# SM2200.net
KiCad netlist of a schematic drawn in Altium Designer
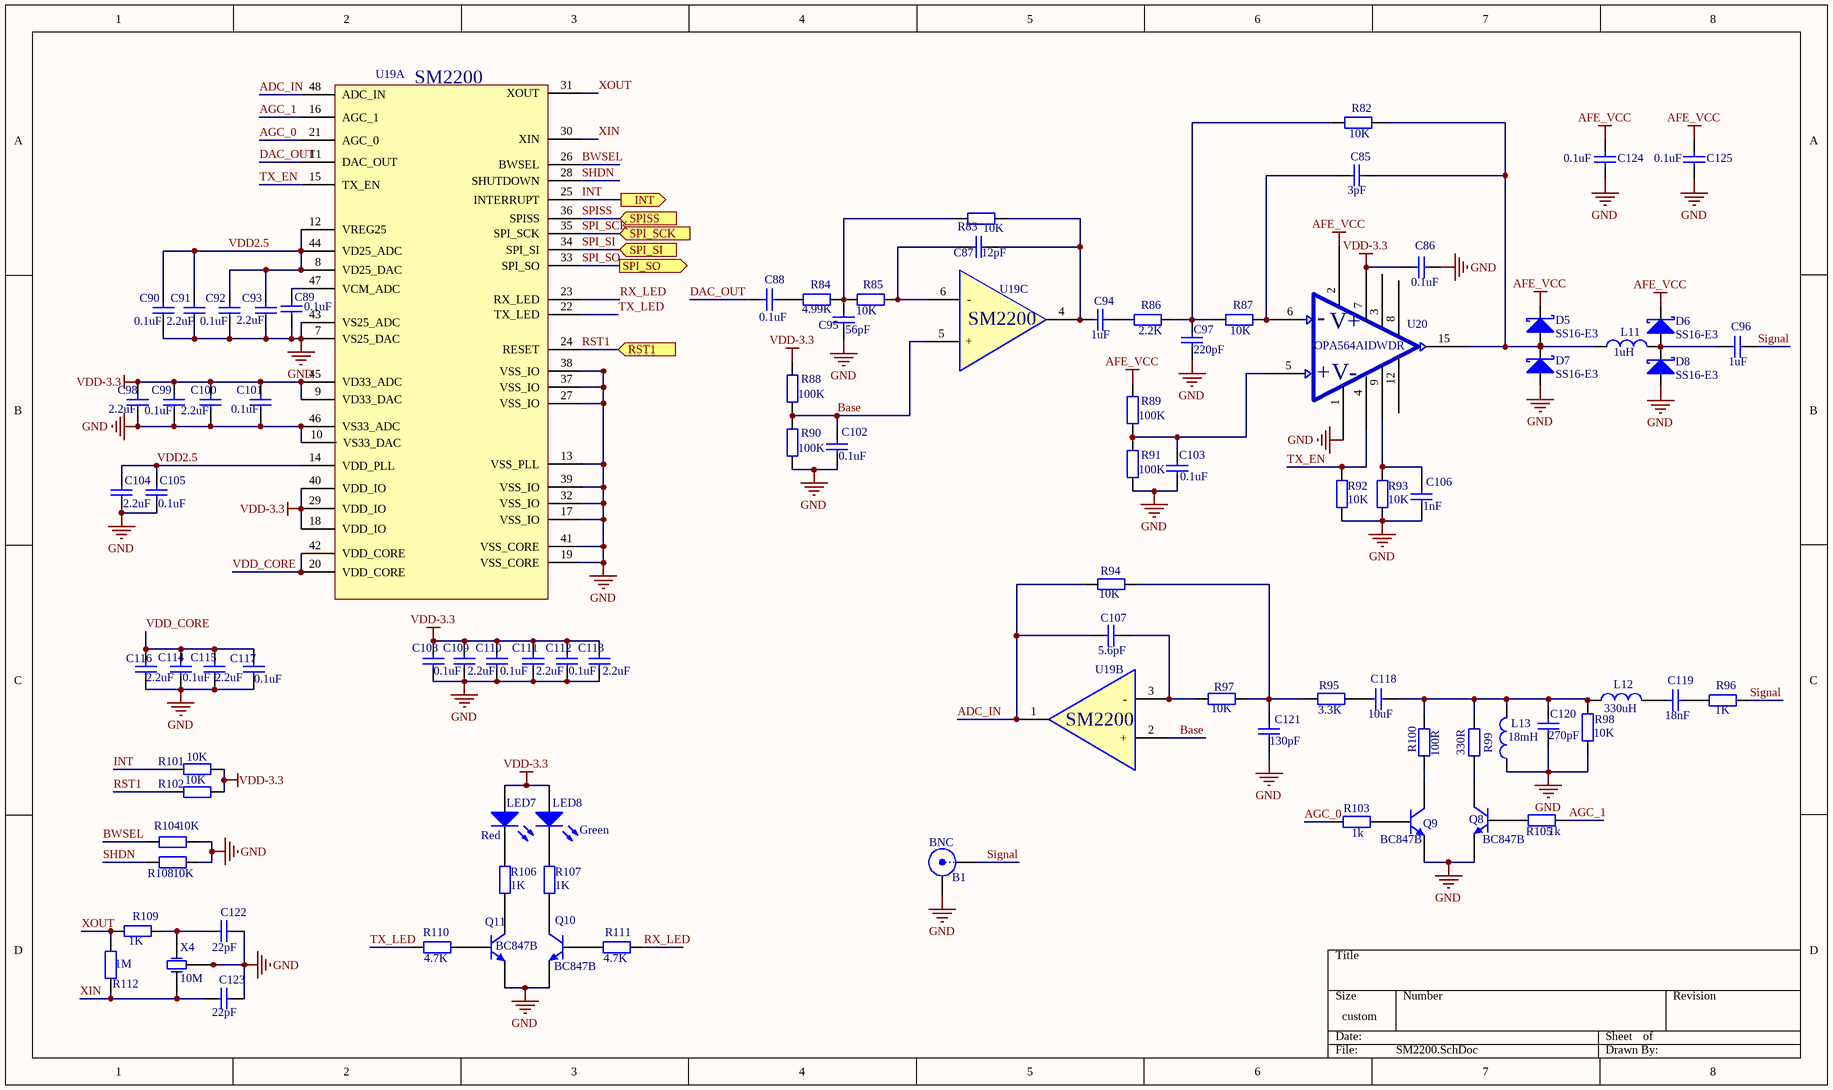
[diagram p0: SM2200.SchDoc]

(export (version "E")
  (design (tool "Eeschema 10.0.6"))
  (components
    (comp (ref "B1")
      (value "BNC")
      (footprint "BNC")
      (fields (field (name "NAME") "BNC"))
      (libsource (lib "原理图库") (part "BNC"))
    )
    (comp (ref "C85")
      (value "3pF")
      (footprint "0603")
      (fields (field (name "Comment") "Capacitor-0603"))
      (libsource (lib "原理图库") (part "Capacitor-0603"))
    )
    (comp (ref "C86")
      (value "0.1uF")
      (footprint "0603")
      (fields (field (name "Comment") "Capacitor-0603"))
      (libsource (lib "原理图库") (part "Capacitor-0603"))
    )
    (comp (ref "C87")
      (value "12pF")
      (footprint "0603")
      (fields (field (name "Comment") "Capacitor-0603"))
      (libsource (lib "原理图库") (part "Capacitor-0603"))
    )
    (comp (ref "C88")
      (value "0.1uF")
      (footprint "0603")
      (fields (field (name "Comment") "Capacitor-0603"))
      (libsource (lib "原理图库") (part "Capacitor-0603"))
    )
    (comp (ref "C89")
      (value "0.1uF")
      (footprint "0603")
      (fields (field (name "Comment") "Capacitor-0805"))
      (libsource (lib "原理图库") (part "Capacitor-0805"))
    )
    (comp (ref "C90")
      (value "0.1uF")
      (footprint "0603")
      (fields (field (name "Comment") "Capacitor-0805"))
      (libsource (lib "原理图库") (part "Capacitor-0805"))
    )
    (comp (ref "C91")
      (value "2.2uF")
      (footprint "0603")
      (fields (field (name "Comment") "Capacitor-0805"))
      (libsource (lib "原理图库") (part "Capacitor-0805"))
    )
    (comp (ref "C92")
      (value "0.1uF")
      (footprint "0603")
      (fields (field (name "Comment") "Capacitor-0805"))
      (libsource (lib "原理图库") (part "Capacitor-0805"))
    )
    (comp (ref "C93")
      (value "2.2uF")
      (footprint "0603")
      (fields (field (name "Comment") "Capacitor-0805"))
      (libsource (lib "原理图库") (part "Capacitor-0805"))
    )
    (comp (ref "C94")
      (value "1uF")
      (footprint "0603")
      (fields (field (name "Comment") "Capacitor-0603"))
      (libsource (lib "原理图库") (part "Capacitor-0603"))
    )
    (comp (ref "C95")
      (value "56pF")
      (footprint "0603")
      (fields (field (name "Comment") "Capacitor-0603"))
      (libsource (lib "原理图库") (part "Capacitor-0603"))
    )
    (comp (ref "C96")
      (value "1uF")
      (footprint "0603")
      (fields (field (name "Comment") "Capacitor-0603"))
      (libsource (lib "原理图库") (part "Capacitor-0603"))
    )
    (comp (ref "C97")
      (value "220pF")
      (footprint "0603")
      (fields (field (name "Comment") "Capacitor-0603"))
      (libsource (lib "原理图库") (part "Capacitor-0603"))
    )
    (comp (ref "C98")
      (value "2.2uF")
      (footprint "0603")
      (fields (field (name "Comment") "Capacitor-0805"))
      (libsource (lib "原理图库") (part "Capacitor-0805"))
    )
    (comp (ref "C99")
      (value "0.1uF")
      (footprint "0603")
      (fields (field (name "Comment") "Capacitor-0805"))
      (libsource (lib "原理图库") (part "Capacitor-0805"))
    )
    (comp (ref "C100")
      (value "2.2uF")
      (footprint "0603")
      (fields (field (name "Comment") "Capacitor-0805"))
      (libsource (lib "原理图库") (part "Capacitor-0805"))
    )
    (comp (ref "C101")
      (value "0.1uF")
      (footprint "0603")
      (fields (field (name "Comment") "Capacitor-0805"))
      (libsource (lib "原理图库") (part "Capacitor-0805"))
    )
    (comp (ref "C102")
      (value "0.1uF")
      (footprint "0603")
      (fields (field (name "Comment") "Capacitor-0603"))
      (libsource (lib "原理图库") (part "Capacitor-0603"))
    )
    (comp (ref "C103")
      (value "0.1uF")
      (footprint "0603")
      (fields (field (name "Comment") "Capacitor-0603"))
      (libsource (lib "原理图库") (part "Capacitor-0603"))
    )
    (comp (ref "C104")
      (value "2.2uF")
      (footprint "0603")
      (fields (field (name "Comment") "Capacitor-0805"))
      (libsource (lib "原理图库") (part "Capacitor-0805"))
    )
    (comp (ref "C105")
      (value "0.1uF")
      (footprint "0603")
      (fields (field (name "Comment") "Capacitor-0805"))
      (libsource (lib "原理图库") (part "Capacitor-0805"))
    )
    (comp (ref "C106")
      (value "1nF")
      (footprint "0603")
      (fields (field (name "Comment") "Capacitor-0603"))
      (libsource (lib "原理图库") (part "Capacitor-0603"))
    )
    (comp (ref "C107")
      (value "5.6pF")
      (footprint "0603")
      (fields (field (name "Comment") "Capacitor-0603"))
      (libsource (lib "原理图库") (part "Capacitor-0603"))
    )
    (comp (ref "C108")
      (value "0.1uF")
      (footprint "0603")
      (fields (field (name "Comment") "Capacitor-0805"))
      (libsource (lib "原理图库") (part "Capacitor-0805"))
    )
    (comp (ref "C109")
      (value "2.2uF")
      (footprint "0603")
      (fields (field (name "Comment") "Capacitor-0805"))
      (libsource (lib "原理图库") (part "Capacitor-0805"))
    )
    (comp (ref "C110")
      (value "0.1uF")
      (footprint "0603")
      (fields (field (name "Comment") "Capacitor-0805"))
      (libsource (lib "原理图库") (part "Capacitor-0805"))
    )
    (comp (ref "C111")
      (value "2.2uF")
      (footprint "0603")
      (fields (field (name "Comment") "Capacitor-0805"))
      (libsource (lib "原理图库") (part "Capacitor-0805"))
    )
    (comp (ref "C112")
      (value "0.1uF")
      (footprint "0603")
      (fields (field (name "Comment") "Capacitor-0805"))
      (libsource (lib "原理图库") (part "Capacitor-0805"))
    )
    (comp (ref "C113")
      (value "2.2uF")
      (footprint "0603")
      (fields (field (name "Comment") "Capacitor-0805"))
      (libsource (lib "原理图库") (part "Capacitor-0805"))
    )
    (comp (ref "C114")
      (value "0.1uF")
      (footprint "0603")
      (fields (field (name "Comment") "Capacitor-0805"))
      (libsource (lib "原理图库") (part "Capacitor-0805"))
    )
    (comp (ref "C115")
      (value "2.2uF")
      (footprint "0603")
      (fields (field (name "Comment") "Capacitor-0805"))
      (libsource (lib "原理图库") (part "Capacitor-0805"))
    )
    (comp (ref "C116")
      (value "2.2uF")
      (footprint "0603")
      (fields (field (name "Comment") "Capacitor-0805"))
      (libsource (lib "原理图库") (part "Capacitor-0805"))
    )
    (comp (ref "C117")
      (value "0.1uF")
      (footprint "0603")
      (fields (field (name "Comment") "Capacitor-0805"))
      (libsource (lib "原理图库") (part "Capacitor-0805"))
    )
    (comp (ref "C118")
      (value "10uF")
      (footprint "0805")
      (fields (field (name "Comment") "Capacitor-0603"))
      (libsource (lib "原理图库") (part "Capacitor-0603"))
    )
    (comp (ref "C119")
      (value "18nF")
      (footprint "0603")
      (fields (field (name "Comment") "Capacitor-0603"))
      (libsource (lib "原理图库") (part "Capacitor-0603"))
    )
    (comp (ref "C120")
      (value "270pF")
      (footprint "0603")
      (fields (field (name "Comment") "Capacitor-0603"))
      (libsource (lib "原理图库") (part "Capacitor-0603"))
    )
    (comp (ref "C121")
      (value "130pF")
      (footprint "0603")
      (fields (field (name "Comment") "Capacitor-0603"))
      (libsource (lib "原理图库") (part "Capacitor-0603"))
    )
    (comp (ref "C122")
      (value "22pF")
      (footprint "0603")
      (fields (field (name "Comment") "Capacitor-0805"))
      (libsource (lib "原理图库") (part "Capacitor-0805"))
    )
    (comp (ref "C123")
      (value "22pF")
      (footprint "0603")
      (fields (field (name "Comment") "Capacitor-0805"))
      (libsource (lib "原理图库") (part "Capacitor-0805"))
    )
    (comp (ref "C124")
      (value "0.1uF")
      (footprint "0603")
      (fields (field (name "Comment") "Capacitor-0603"))
      (libsource (lib "原理图库") (part "Capacitor-0603"))
    )
    (comp (ref "C125")
      (value "0.1uF")
      (footprint "0603")
      (fields (field (name "Comment") "Capacitor-0603"))
      (libsource (lib "原理图库") (part "Capacitor-0603"))
    )
    (comp (ref "D5")
      (value "SSA34")
      (footprint "IN5824")
      (fields (field (name "NAME") "SS16-E3"))
      (libsource (lib "原理图库") (part "SSA34"))
    )
    (comp (ref "D6")
      (value "SSA34")
      (footprint "IN5824")
      (fields (field (name "NAME") "SS16-E3"))
      (libsource (lib "原理图库") (part "SSA34"))
    )
    (comp (ref "D7")
      (value "SSA34")
      (footprint "IN5824")
      (fields (field (name "NAME") "SS16-E3"))
      (libsource (lib "原理图库") (part "SSA34"))
    )
    (comp (ref "D8")
      (value "SSA34")
      (footprint "IN5824")
      (fields (field (name "NAME") "SS16-E3"))
      (libsource (lib "原理图库") (part "SSA34"))
    )
    (comp (ref "L11")
      (value "1uH")
      (footprint "1206")
      (fields (field (name "Comment") "Inductor"))
      (libsource (lib "原理图库") (part "Inductor"))
    )
    (comp (ref "L12")
      (value "330uH")
      (footprint "Inductor(7.8*7*5)")
      (fields (field (name "Comment") "Inductor"))
      (libsource (lib "原理图库") (part "Inductor"))
    )
    (comp (ref "L13")
      (value "18mH")
      (footprint "工字电感0608")
      (fields (field (name "Comment") "Inductor"))
      (libsource (lib "原理图库") (part "Inductor"))
    )
    (comp (ref "LED7")
      (value "LED")
      (footprint "外插小灯")
      (fields (field (name "COLOR") "Red"))
      (libsource (lib "原理图库") (part "LED"))
    )
    (comp (ref "LED8")
      (value "LED")
      (footprint "外插小灯")
      (fields (field (name "COLOR") "Green"))
      (libsource (lib "原理图库") (part "LED"))
    )
    (comp (ref "Q8")
      (value "BC847")
      (footprint "BC847B")
      (fields (field (name "NAME") "BC847B"))
      (libsource (lib "原理图库") (part "BC847"))
    )
    (comp (ref "Q9")
      (value "BC847")
      (footprint "BC847B")
      (fields (field (name "NAME") "BC847B"))
      (libsource (lib "原理图库") (part "BC847"))
    )
    (comp (ref "Q10")
      (value "BC847")
      (footprint "BC847B")
      (fields (field (name "NAME") "BC847B"))
      (libsource (lib "原理图库") (part "BC847"))
    )
    (comp (ref "Q11")
      (value "BC847")
      (footprint "BC847B")
      (fields (field (name "NAME") "BC847B"))
      (libsource (lib "原理图库") (part "BC847"))
    )
    (comp (ref "R82")
      (value "10K")
      (footprint "0603")
      (fields (field (name "Comment") "Resistor-0603"))
      (libsource (lib "原理图库") (part "Resistor-0603"))
    )
    (comp (ref "R83")
      (value "10K")
      (footprint "0603")
      (fields (field (name "Comment") "Resistor-0603"))
      (libsource (lib "原理图库") (part "Resistor-0603"))
    )
    (comp (ref "R84")
      (value "4.99K")
      (footprint "0603")
      (fields (field (name "Comment") "Resistor-0603"))
      (libsource (lib "原理图库") (part "Resistor-0603"))
    )
    (comp (ref "R85")
      (value "10K")
      (footprint "0603")
      (fields (field (name "Comment") "Resistor-0603"))
      (libsource (lib "原理图库") (part "Resistor-0603"))
    )
    (comp (ref "R86")
      (value "2.2K")
      (footprint "0603")
      (fields (field (name "Comment") "Resistor-0603"))
      (libsource (lib "原理图库") (part "Resistor-0603"))
    )
    (comp (ref "R87")
      (value "10K")
      (footprint "0603")
      (fields (field (name "Comment") "Resistor-0603"))
      (libsource (lib "原理图库") (part "Resistor-0603"))
    )
    (comp (ref "R88")
      (value "100K")
      (footprint "0603")
      (fields (field (name "Comment") "Resistor-0603"))
      (libsource (lib "") (part "Resistor-0603_2"))
    )
    (comp (ref "R89")
      (value "100K")
      (footprint "0603")
      (fields (field (name "Comment") "Resistor-0603"))
      (libsource (lib "") (part "Resistor-0603_2"))
    )
    (comp (ref "R90")
      (value "100K")
      (footprint "0603")
      (fields (field (name "Comment") "Resistor-0603"))
      (libsource (lib "") (part "Resistor-0603_2"))
    )
    (comp (ref "R91")
      (value "100K")
      (footprint "0603")
      (fields (field (name "Comment") "Resistor-0603"))
      (libsource (lib "") (part "Resistor-0603_2"))
    )
    (comp (ref "R92")
      (value "10K")
      (footprint "0603")
      (fields (field (name "Comment") "Resistor-0603"))
      (libsource (lib "") (part "Resistor-0603_2"))
    )
    (comp (ref "R93")
      (value "10K")
      (footprint "0603")
      (fields (field (name "Comment") "Resistor-0603"))
      (libsource (lib "") (part "Resistor-0603_2"))
    )
    (comp (ref "R94")
      (value "10K")
      (footprint "0603")
      (fields (field (name "Comment") "Resistor-0603"))
      (libsource (lib "") (part "Resistor-0603_1"))
    )
    (comp (ref "R95")
      (value "3.3K")
      (footprint "0603")
      (fields (field (name "Comment") "Resistor-0603"))
      (libsource (lib "") (part "Resistor-0603_1"))
    )
    (comp (ref "R96")
      (value "1K")
      (footprint "0603")
      (fields (field (name "Comment") "Resistor-0603"))
      (libsource (lib "原理图库") (part "Resistor-0603"))
    )
    (comp (ref "R97")
      (value "10K")
      (footprint "0603")
      (fields (field (name "Comment") "Resistor-0603"))
      (libsource (lib "") (part "Resistor-0603_1"))
    )
    (comp (ref "R98")
      (value "10K")
      (footprint "0603")
      (fields (field (name "Comment") "Resistor-0603"))
      (libsource (lib "") (part "Resistor-0603_2"))
    )
    (comp (ref "R99")
      (value "330R")
      (footprint "0603")
      (fields (field (name "Comment") "Resistor-0603"))
      (libsource (lib "") (part "Resistor-0603_2"))
    )
    (comp (ref "R100")
      (value "100R")
      (footprint "0603")
      (fields (field (name "Comment") "Resistor-0603"))
      (libsource (lib "") (part "Resistor-0603_2"))
    )
    (comp (ref "R101")
      (value "10K")
      (footprint "0603")
      (fields (field (name "Comment") "Resistor-0805"))
      (libsource (lib "") (part "Resistor-0805_1"))
    )
    (comp (ref "R102")
      (value "10K")
      (footprint "0603")
      (fields (field (name "Comment") "Resistor-0805"))
      (libsource (lib "") (part "Resistor-0805_1"))
    )
    (comp (ref "R103")
      (value "1k")
      (footprint "0603")
      (fields (field (name "Comment") "Resistor-0603"))
      (libsource (lib "") (part "Resistor-0603_1"))
    )
    (comp (ref "R104")
      (value "10K")
      (footprint "0603")
      (fields (field (name "Comment") "Resistor-0805"))
      (libsource (lib "") (part "Resistor-0805_1"))
    )
    (comp (ref "R105")
      (value "1k")
      (footprint "0603")
      (fields (field (name "Comment") "Resistor-0603"))
      (libsource (lib "原理图库") (part "Resistor-0603"))
    )
    (comp (ref "R106")
      (value "1K")
      (footprint "0603")
      (fields (field (name "Comment") "Resistor-0805"))
      (libsource (lib "原理图库") (part "Resistor-0805"))
    )
    (comp (ref "R107")
      (value "1K")
      (footprint "0603")
      (fields (field (name "Comment") "Resistor-0805"))
      (libsource (lib "原理图库") (part "Resistor-0805"))
    )
    (comp (ref "R108")
      (value "10K")
      (footprint "0603")
      (fields (field (name "Comment") "Resistor-0805"))
      (libsource (lib "") (part "Resistor-0805_1"))
    )
    (comp (ref "R109")
      (value "1K")
      (footprint "0603")
      (fields (field (name "Comment") "Resistor-0805"))
      (libsource (lib "") (part "Resistor-0805_1"))
    )
    (comp (ref "R110")
      (value "4.7K")
      (footprint "0603")
      (fields (field (name "Comment") "Resistor-0805"))
      (libsource (lib "") (part "Resistor-0805_2"))
    )
    (comp (ref "R111")
      (value "4.7K")
      (footprint "0603")
      (fields (field (name "Comment") "Resistor-0805"))
      (libsource (lib "") (part "Resistor-0805_2"))
    )
    (comp (ref "R112")
      (value "1M")
      (footprint "0603")
      (fields (field (name "Comment") "Resistor-0805"))
      (libsource (lib "原理图库") (part "Resistor-0805"))
    )
    (comp (ref "U19")
      (value "SM2200")
      (footprint "SM2200")
      (fields (field (name "ALTIUM_UNNAMED_1") "SM2200"))
      (libsource (lib "") (part "SM2200_1"))
    )
    (comp (ref "U20")
      (value "OPA564AIDWDR")
      (footprint "OPA564AIDWDR")
      (fields (field (name "NAME") "OPA564AIDWDR"))
      (libsource (lib "原理图库") (part "OPA564AIDWDR"))
    )
    (comp (ref "X4")
      (value "10M")
      (footprint "3225无源晶振")
      (fields (field (name "Comment") "3225无源晶振"))
      (libsource (lib "原理图库") (part "3225无源晶振"))
    )
  )
  (nets
    (net (code "1") (name "/ADC_IN") (class "Default")
      (node (ref "C107") (pin "1") (pinfunction "1_1") (pintype "passive"))
      (node (ref "R94") (pin "2") (pinfunction "2_2") (pintype "passive"))
      (node (ref "U19") (pin "1") (pintype "passive"))
      (node (ref "U19") (pin "48") (pinfunction "ADC_IN_48") (pintype "passive"))
    )
    (net (code "2") (name "/AGC_0") (class "Default")
      (node (ref "R103") (pin "2") (pinfunction "2_2") (pintype "passive"))
      (node (ref "U19") (pin "21") (pinfunction "AGC_0_21") (pintype "passive"))
    )
    (net (code "3") (name "/AGC_1") (class "Default")
      (node (ref "R105") (pin "2") (pinfunction "2_2") (pintype "passive"))
      (node (ref "U19") (pin "16") (pinfunction "AGC_1_16") (pintype "passive"))
    )
    (net (code "4") (name "/BWSEL") (class "Default")
      (node (ref "R104") (pin "1") (pinfunction "1_1") (pintype "passive"))
      (node (ref "U19") (pin "26") (pinfunction "BWSEL_26") (pintype "passive"))
    )
    (net (code "5") (name "/Base") (class "Default")
      (node (ref "C102") (pin "2") (pinfunction "2_2") (pintype "passive"))
      (node (ref "R88") (pin "1") (pinfunction "1_1") (pintype "passive"))
      (node (ref "R90") (pin "2") (pinfunction "2_2") (pintype "passive"))
      (node (ref "U19") (pin "2") (pinfunction "+_2") (pintype "passive"))
      (node (ref "U19") (pin "5") (pinfunction "+_5") (pintype "passive"))
    )
    (net (code "6") (name "/DAC_OUT") (class "Default")
      (node (ref "C88") (pin "2") (pinfunction "2_2") (pintype "passive"))
      (node (ref "U19") (pin "11") (pinfunction "DAC_OUT_11") (pintype "passive"))
    )
    (net (code "7") (name "/INT") (class "Default")
      (node (ref "R101") (pin "1") (pinfunction "1_1") (pintype "passive"))
      (node (ref "U19") (pin "25") (pinfunction "INTERRUPT_25") (pintype "passive"))
    )
    (net (code "8") (name "/RST1") (class "Default")
      (node (ref "R102") (pin "1") (pinfunction "1_1") (pintype "passive"))
      (node (ref "U19") (pin "24") (pinfunction "RESET_24") (pintype "passive"))
    )
    (net (code "9") (name "/RX_LED") (class "Default")
      (node (ref "R111") (pin "1") (pinfunction "1_1") (pintype "passive"))
      (node (ref "U19") (pin "23") (pinfunction "RX_LED_23") (pintype "passive"))
    )
    (net (code "10") (name "/SHDN") (class "Default")
      (node (ref "R108") (pin "1") (pinfunction "1_1") (pintype "passive"))
      (node (ref "U19") (pin "28") (pinfunction "SHUTDOWN_28") (pintype "passive"))
    )
    (net (code "11") (name "/SPISS") (class "Default")
      (node (ref "U19") (pin "36") (pinfunction "SPISS_36") (pintype "passive"))
    )
    (net (code "12") (name "/SPI_SCK") (class "Default")
      (node (ref "U19") (pin "35") (pinfunction "SPI_SCK_35") (pintype "passive"))
    )
    (net (code "13") (name "/SPI_SI") (class "Default")
      (node (ref "U19") (pin "34") (pinfunction "SPI_SI_34") (pintype "passive"))
    )
    (net (code "14") (name "/SPI_SO") (class "Default")
      (node (ref "U19") (pin "33") (pinfunction "SPI_SO_33") (pintype "passive"))
    )
    (net (code "15") (name "/Signal") (class "Default")
      (node (ref "B1") (pin "2") (pinfunction "X_2") (pintype "passive"))
      (node (ref "C96") (pin "1") (pinfunction "1_1") (pintype "passive"))
      (node (ref "R96") (pin "2") (pinfunction "2_2") (pintype "passive"))
    )
    (net (code "16") (name "/TX_EN") (class "Default")
      (node (ref "R92") (pin "2") (pinfunction "2_2") (pintype "passive"))
      (node (ref "U19") (pin "15") (pinfunction "TX_EN_15") (pintype "passive"))
      (node (ref "U20") (pin "4") (pintype "passive"))
    )
    (net (code "17") (name "/TX_LED") (class "Default")
      (node (ref "R110") (pin "2") (pinfunction "2_2") (pintype "passive"))
      (node (ref "U19") (pin "22") (pinfunction "TX_LED_22") (pintype "passive"))
    )
    (net (code "18") (name "/VDD2.5") (class "Default")
      (node (ref "C104") (pin "2") (pinfunction "2_2") (pintype "passive"))
      (node (ref "C105") (pin "2") (pinfunction "2_2") (pintype "passive"))
      (node (ref "C90") (pin "2") (pinfunction "2_2") (pintype "passive"))
      (node (ref "C91") (pin "2") (pinfunction "2_2") (pintype "passive"))
      (node (ref "C92") (pin "2") (pinfunction "2_2") (pintype "passive"))
      (node (ref "C93") (pin "2") (pinfunction "2_2") (pintype "passive"))
      (node (ref "U19") (pin "12") (pinfunction "VREG25_12") (pintype "passive"))
      (node (ref "U19") (pin "14") (pinfunction "VDD_PLL_14") (pintype "passive"))
      (node (ref "U19") (pin "44") (pinfunction "VD25_ADC_44") (pintype "passive"))
      (node (ref "U19") (pin "8") (pinfunction "VD25_DAC_8") (pintype "passive"))
    )
    (net (code "19") (name "/VDD_CORE") (class "Default")
      (node (ref "C114") (pin "2") (pinfunction "2_2") (pintype "passive"))
      (node (ref "C115") (pin "2") (pinfunction "2_2") (pintype "passive"))
      (node (ref "C116") (pin "2") (pinfunction "2_2") (pintype "passive"))
      (node (ref "C117") (pin "2") (pinfunction "2_2") (pintype "passive"))
      (node (ref "U19") (pin "20") (pinfunction "VDD_CORE_20") (pintype "passive"))
      (node (ref "U19") (pin "42") (pinfunction "VDD_CORE_42") (pintype "passive"))
    )
    (net (code "20") (name "/XIN") (class "Default")
      (node (ref "C123") (pin "1") (pinfunction "1_1") (pintype "passive"))
      (node (ref "R112") (pin "1") (pinfunction "1_1") (pintype "passive"))
      (node (ref "U19") (pin "30") (pinfunction "XIN_30") (pintype "passive"))
      (node (ref "X4") (pin "1") (pinfunction "OSC1_1") (pintype "passive"))
    )
    (net (code "21") (name "/XOUT") (class "Default")
      (node (ref "R109") (pin "1") (pinfunction "1_1") (pintype "passive"))
      (node (ref "R112") (pin "2") (pinfunction "2_2") (pintype "passive"))
      (node (ref "U19") (pin "31") (pinfunction "XOUT_31") (pintype "passive"))
    )
    (net (code "22") (name "AFE_VCC") (class "Default")
      (node (ref "C124") (pin "2") (pinfunction "2_2") (pintype "passive"))
      (node (ref "C125") (pin "2") (pinfunction "2_2") (pintype "passive"))
      (node (ref "D5") (pin "2") (pinfunction "K_2") (pintype "passive"))
      (node (ref "D6") (pin "2") (pinfunction "K_2") (pintype "passive"))
      (node (ref "R89") (pin "2") (pinfunction "2_2") (pintype "passive"))
      (node (ref "U20") (pin "2") (pintype "passive"))
    )
    (net (code "23") (name "GND") (class "Default")
      (node (ref "B1") (pin "1") (pinfunction "Y_1") (pintype "passive"))
      (node (ref "C100") (pin "1") (pinfunction "1_1") (pintype "passive"))
      (node (ref "C101") (pin "1") (pinfunction "1_1") (pintype "passive"))
      (node (ref "C102") (pin "1") (pinfunction "1_1") (pintype "passive"))
      (node (ref "C103") (pin "2") (pinfunction "2_2") (pintype "passive"))
      (node (ref "C104") (pin "1") (pinfunction "1_1") (pintype "passive"))
      (node (ref "C105") (pin "1") (pinfunction "1_1") (pintype "passive"))
      (node (ref "C106") (pin "1") (pinfunction "1_1") (pintype "passive"))
      (node (ref "C108") (pin "1") (pinfunction "1_1") (pintype "passive"))
      (node (ref "C109") (pin "1") (pinfunction "1_1") (pintype "passive"))
      (node (ref "C110") (pin "1") (pinfunction "1_1") (pintype "passive"))
      (node (ref "C111") (pin "1") (pinfunction "1_1") (pintype "passive"))
      (node (ref "C112") (pin "1") (pinfunction "1_1") (pintype "passive"))
      (node (ref "C113") (pin "1") (pinfunction "1_1") (pintype "passive"))
      (node (ref "C114") (pin "1") (pinfunction "1_1") (pintype "passive"))
      (node (ref "C115") (pin "1") (pinfunction "1_1") (pintype "passive"))
      (node (ref "C116") (pin "1") (pinfunction "1_1") (pintype "passive"))
      (node (ref "C117") (pin "1") (pinfunction "1_1") (pintype "passive"))
      (node (ref "C120") (pin "2") (pinfunction "2_2") (pintype "passive"))
      (node (ref "C121") (pin "2") (pinfunction "2_2") (pintype "passive"))
      (node (ref "C122") (pin "2") (pinfunction "2_2") (pintype "passive"))
      (node (ref "C123") (pin "2") (pinfunction "2_2") (pintype "passive"))
      (node (ref "C124") (pin "1") (pinfunction "1_1") (pintype "passive"))
      (node (ref "C125") (pin "1") (pinfunction "1_1") (pintype "passive"))
      (node (ref "C86") (pin "1") (pinfunction "1_1") (pintype "passive"))
      (node (ref "C89") (pin "1") (pinfunction "1_1") (pintype "passive"))
      (node (ref "C90") (pin "1") (pinfunction "1_1") (pintype "passive"))
      (node (ref "C91") (pin "1") (pinfunction "1_1") (pintype "passive"))
      (node (ref "C92") (pin "1") (pinfunction "1_1") (pintype "passive"))
      (node (ref "C93") (pin "1") (pinfunction "1_1") (pintype "passive"))
      (node (ref "C95") (pin "1") (pinfunction "1_1") (pintype "passive"))
      (node (ref "C97") (pin "2") (pinfunction "2_2") (pintype "passive"))
      (node (ref "C98") (pin "1") (pinfunction "1_1") (pintype "passive"))
      (node (ref "C99") (pin "1") (pinfunction "1_1") (pintype "passive"))
      (node (ref "D7") (pin "1") (pinfunction "A_1") (pintype "passive"))
      (node (ref "D8") (pin "1") (pinfunction "A_1") (pintype "passive"))
      (node (ref "L13") (pin "1") (pinfunction "1_1") (pintype "passive"))
      (node (ref "Q10") (pin "1") (pinfunction "E_1") (pintype "passive"))
      (node (ref "Q11") (pin "1") (pinfunction "E_1") (pintype "passive"))
      (node (ref "Q8") (pin "1") (pinfunction "E_1") (pintype "passive"))
      (node (ref "Q9") (pin "1") (pinfunction "E_1") (pintype "passive"))
      (node (ref "R104") (pin "2") (pinfunction "2_2") (pintype "passive"))
      (node (ref "R108") (pin "2") (pinfunction "2_2") (pintype "passive"))
      (node (ref "R90") (pin "1") (pinfunction "1_1") (pintype "passive"))
      (node (ref "R91") (pin "1") (pinfunction "1_1") (pintype "passive"))
      (node (ref "R92") (pin "1") (pinfunction "1_1") (pintype "passive"))
      (node (ref "R93") (pin "1") (pinfunction "1_1") (pintype "passive"))
      (node (ref "R98") (pin "1") (pinfunction "1_1") (pintype "passive"))
      (node (ref "U19") (pin "10") (pinfunction "VS33_DAC_10") (pintype "passive"))
      (node (ref "U19") (pin "13") (pinfunction "VSS_PLL_13") (pintype "passive"))
      (node (ref "U19") (pin "17") (pinfunction "VSS_IO_17") (pintype "passive"))
      (node (ref "U19") (pin "19") (pinfunction "VSS_CORE_19") (pintype "passive"))
      (node (ref "U19") (pin "27") (pinfunction "VSS_IO_27") (pintype "passive"))
      (node (ref "U19") (pin "32") (pinfunction "VSS_IO_32") (pintype "passive"))
      (node (ref "U19") (pin "37") (pinfunction "VSS_IO_37") (pintype "passive"))
      (node (ref "U19") (pin "38") (pinfunction "VSS_IO_38") (pintype "passive"))
      (node (ref "U19") (pin "39") (pinfunction "VSS_IO_39") (pintype "passive"))
      (node (ref "U19") (pin "41") (pinfunction "VSS_CORE_41") (pintype "passive"))
      (node (ref "U19") (pin "43") (pinfunction "VS25_ADC_43") (pintype "passive"))
      (node (ref "U19") (pin "46") (pinfunction "VS33_ADC_46") (pintype "passive"))
      (node (ref "U19") (pin "7") (pinfunction "VS25_DAC_7") (pintype "passive"))
      (node (ref "U20") (pin "1") (pintype "passive"))
      (node (ref "X4") (pin "2") (pinfunction "GND_2") (pintype "passive"))
      (node (ref "X4") (pin "4") (pinfunction "GND_4") (pintype "passive"))
    )
    (net (code "24") (name "Net-(C87-Pad1)") (class "Default")
      (node (ref "C87") (pin "1") (pinfunction "1_1") (pintype "passive"))
      (node (ref "C94") (pin "2") (pinfunction "2_2") (pintype "passive"))
      (node (ref "R83") (pin "2") (pinfunction "2_2") (pintype "passive"))
      (node (ref "U19") (pin "4") (pintype "passive"))
    )
    (net (code "25") (name "Net-(C88-Pad1)") (class "Default")
      (node (ref "C88") (pin "1") (pinfunction "1_1") (pintype "passive"))
      (node (ref "R84") (pin "1") (pinfunction "1_1") (pintype "passive"))
    )
    (net (code "26") (name "Net-(C94-Pad1)") (class "Default")
      (node (ref "C94") (pin "1") (pinfunction "1_1") (pintype "passive"))
      (node (ref "R86") (pin "1") (pinfunction "1_1") (pintype "passive"))
    )
    (net (code "27") (name "Net-(C95-Pad2)") (class "Default")
      (node (ref "C95") (pin "2") (pinfunction "2_2") (pintype "passive"))
      (node (ref "R83") (pin "1") (pinfunction "1_1") (pintype "passive"))
      (node (ref "R84") (pin "2") (pinfunction "2_2") (pintype "passive"))
      (node (ref "R85") (pin "1") (pinfunction "1_1") (pintype "passive"))
    )
    (net (code "28") (name "Net-(C97-Pad1)") (class "Default")
      (node (ref "C97") (pin "1") (pinfunction "1_1") (pintype "passive"))
      (node (ref "R82") (pin "1") (pinfunction "1_1") (pintype "passive"))
      (node (ref "R86") (pin "2") (pinfunction "2_2") (pintype "passive"))
      (node (ref "R87") (pin "1") (pinfunction "1_1") (pintype "passive"))
    )
    (net (code "29") (name "Net-(C106-Pad2)") (class "Default")
      (node (ref "C106") (pin "2") (pinfunction "2_2") (pintype "passive"))
      (node (ref "R93") (pin "2") (pinfunction "2_2") (pintype "passive"))
      (node (ref "U20") (pin "9") (pintype "passive"))
    )
    (net (code "30") (name "Net-(C118-Pad1)") (class "Default")
      (node (ref "C118") (pin "1") (pinfunction "1_1") (pintype "passive"))
      (node (ref "C120") (pin "1") (pinfunction "1_1") (pintype "passive"))
      (node (ref "L12") (pin "1") (pinfunction "1_1") (pintype "passive"))
      (node (ref "L13") (pin "2") (pinfunction "2_2") (pintype "passive"))
      (node (ref "R100") (pin "2") (pinfunction "2_2") (pintype "passive"))
      (node (ref "R98") (pin "2") (pinfunction "2_2") (pintype "passive"))
      (node (ref "R99") (pin "2") (pinfunction "2_2") (pintype "passive"))
    )
    (net (code "31") (name "Net-(C118-Pad2)") (class "Default")
      (node (ref "C118") (pin "2") (pinfunction "2_2") (pintype "passive"))
      (node (ref "R95") (pin "1") (pinfunction "1_1") (pintype "passive"))
    )
    (net (code "32") (name "Net-(C119-Pad1)") (class "Default")
      (node (ref "C119") (pin "1") (pinfunction "1_1") (pintype "passive"))
      (node (ref "R96") (pin "1") (pinfunction "1_1") (pintype "passive"))
    )
    (net (code "33") (name "Net-(C119-Pad2)") (class "Default")
      (node (ref "C119") (pin "2") (pinfunction "2_2") (pintype "passive"))
      (node (ref "L12") (pin "2") (pinfunction "2_2") (pintype "passive"))
    )
    (net (code "34") (name "Net-(C121-Pad1)") (class "Default")
      (node (ref "C121") (pin "1") (pinfunction "1_1") (pintype "passive"))
      (node (ref "R94") (pin "1") (pinfunction "1_1") (pintype "passive"))
      (node (ref "R95") (pin "2") (pinfunction "2_2") (pintype "passive"))
      (node (ref "R97") (pin "1") (pinfunction "1_1") (pintype "passive"))
    )
    (net (code "35") (name "Net-(D5-A)") (class "Default")
      (node (ref "C85") (pin "1") (pinfunction "1_1") (pintype "passive"))
      (node (ref "D5") (pin "1") (pinfunction "A_1") (pintype "passive"))
      (node (ref "D7") (pin "2") (pinfunction "K_2") (pintype "passive"))
      (node (ref "L11") (pin "1") (pinfunction "1_1") (pintype "passive"))
      (node (ref "R82") (pin "2") (pinfunction "2_2") (pintype "passive"))
      (node (ref "U20") (pin "15") (pintype "passive"))
    )
    (net (code "36") (name "Net-(D6-A)") (class "Default")
      (node (ref "C96") (pin "2") (pinfunction "2_2") (pintype "passive"))
      (node (ref "D6") (pin "1") (pinfunction "A_1") (pintype "passive"))
      (node (ref "D8") (pin "2") (pinfunction "K_2") (pintype "passive"))
      (node (ref "L11") (pin "2") (pinfunction "2_2") (pintype "passive"))
    )
    (net (code "37") (name "Net-(LED7-Pad2)") (class "Default")
      (node (ref "LED7") (pin "2") (pinfunction "2_2") (pintype "passive"))
      (node (ref "R106") (pin "2") (pinfunction "2_2") (pintype "passive"))
    )
    (net (code "38") (name "Net-(LED8-Pad2)") (class "Default")
      (node (ref "LED8") (pin "2") (pinfunction "2_2") (pintype "passive"))
      (node (ref "R107") (pin "2") (pinfunction "2_2") (pintype "passive"))
    )
    (net (code "39") (name "Net-(Q8-B)") (class "Default")
      (node (ref "Q8") (pin "2") (pinfunction "B_2") (pintype "passive"))
      (node (ref "R105") (pin "1") (pinfunction "1_1") (pintype "passive"))
    )
    (net (code "40") (name "Net-(Q8-C)") (class "Default")
      (node (ref "Q8") (pin "3") (pinfunction "C_3") (pintype "passive"))
      (node (ref "R99") (pin "1") (pinfunction "1_1") (pintype "passive"))
    )
    (net (code "41") (name "Net-(Q9-B)") (class "Default")
      (node (ref "Q9") (pin "2") (pinfunction "B_2") (pintype "passive"))
      (node (ref "R103") (pin "1") (pinfunction "1_1") (pintype "passive"))
    )
    (net (code "42") (name "Net-(Q9-C)") (class "Default")
      (node (ref "Q9") (pin "3") (pinfunction "C_3") (pintype "passive"))
      (node (ref "R100") (pin "1") (pinfunction "1_1") (pintype "passive"))
    )
    (net (code "43") (name "Net-(Q10-B)") (class "Default")
      (node (ref "Q10") (pin "2") (pinfunction "B_2") (pintype "passive"))
      (node (ref "R111") (pin "2") (pinfunction "2_2") (pintype "passive"))
    )
    (net (code "44") (name "Net-(Q10-C)") (class "Default")
      (node (ref "Q10") (pin "3") (pinfunction "C_3") (pintype "passive"))
      (node (ref "R107") (pin "1") (pinfunction "1_1") (pintype "passive"))
    )
    (net (code "45") (name "Net-(Q11-B)") (class "Default")
      (node (ref "Q11") (pin "2") (pinfunction "B_2") (pintype "passive"))
      (node (ref "R110") (pin "1") (pinfunction "1_1") (pintype "passive"))
    )
    (net (code "46") (name "Net-(Q11-C)") (class "Default")
      (node (ref "Q11") (pin "3") (pinfunction "C_3") (pintype "passive"))
      (node (ref "R106") (pin "1") (pinfunction "1_1") (pintype "passive"))
    )
    (net (code "47") (name "Net-(U19A-VCM_ADC)") (class "Default")
      (node (ref "C89") (pin "2") (pinfunction "2_2") (pintype "passive"))
      (node (ref "U19") (pin "47") (pinfunction "VCM_ADC_47") (pintype "passive"))
    )
    (net (code "48") (name "Net-(U19B--)") (class "Default")
      (node (ref "C107") (pin "2") (pinfunction "2_2") (pintype "passive"))
      (node (ref "R97") (pin "2") (pinfunction "2_2") (pintype "passive"))
      (node (ref "U19") (pin "3") (pinfunction "-_3") (pintype "passive"))
    )
    (net (code "49") (name "Net-(U19C--)") (class "Default")
      (node (ref "C87") (pin "2") (pinfunction "2_2") (pintype "passive"))
      (node (ref "R85") (pin "2") (pinfunction "2_2") (pintype "passive"))
      (node (ref "U19") (pin "6") (pinfunction "-_6") (pintype "passive"))
    )
    (net (code "50") (name "Net-(U20-9)") (class "Default")
      (node (ref "C85") (pin "2") (pinfunction "2_2") (pintype "passive"))
      (node (ref "R87") (pin "2") (pinfunction "2_2") (pintype "passive"))
      (node (ref "U20") (pin "6") (pinfunction "9_6") (pintype "passive"))
    )
    (net (code "51") (name "Net-(U20-10)") (class "Default")
      (node (ref "C103") (pin "1") (pinfunction "1_1") (pintype "passive"))
      (node (ref "R89") (pin "1") (pinfunction "1_1") (pintype "passive"))
      (node (ref "R91") (pin "2") (pinfunction "2_2") (pintype "passive"))
      (node (ref "U20") (pin "5") (pinfunction "10_5") (pintype "passive"))
    )
    (net (code "52") (name "Net-(X4-OSC2)") (class "Default")
      (node (ref "C122") (pin "1") (pinfunction "1_1") (pintype "passive"))
      (node (ref "R109") (pin "2") (pinfunction "2_2") (pintype "passive"))
      (node (ref "X4") (pin "3") (pinfunction "OSC2_3") (pintype "passive"))
    )
    (net (code "53") (name "VDD-3.3") (class "Default")
      (node (ref "C100") (pin "2") (pinfunction "2_2") (pintype "passive"))
      (node (ref "C101") (pin "2") (pinfunction "2_2") (pintype "passive"))
      (node (ref "C108") (pin "2") (pinfunction "2_2") (pintype "passive"))
      (node (ref "C109") (pin "2") (pinfunction "2_2") (pintype "passive"))
      (node (ref "C110") (pin "2") (pinfunction "2_2") (pintype "passive"))
      (node (ref "C111") (pin "2") (pinfunction "2_2") (pintype "passive"))
      (node (ref "C112") (pin "2") (pinfunction "2_2") (pintype "passive"))
      (node (ref "C113") (pin "2") (pinfunction "2_2") (pintype "passive"))
      (node (ref "C86") (pin "2") (pinfunction "2_2") (pintype "passive"))
      (node (ref "C98") (pin "2") (pinfunction "2_2") (pintype "passive"))
      (node (ref "C99") (pin "2") (pinfunction "2_2") (pintype "passive"))
      (node (ref "LED7") (pin "1") (pinfunction "A_1") (pintype "passive"))
      (node (ref "LED8") (pin "1") (pinfunction "A_1") (pintype "passive"))
      (node (ref "R101") (pin "2") (pinfunction "2_2") (pintype "passive"))
      (node (ref "R102") (pin "2") (pinfunction "2_2") (pintype "passive"))
      (node (ref "R88") (pin "2") (pinfunction "2_2") (pintype "passive"))
      (node (ref "U19") (pin "18") (pinfunction "VDD_IO_18") (pintype "passive"))
      (node (ref "U19") (pin "29") (pinfunction "VDD_IO_29") (pintype "passive"))
      (node (ref "U19") (pin "40") (pinfunction "VDD_IO_40") (pintype "passive"))
      (node (ref "U19") (pin "45") (pinfunction "VD33_ADC_45") (pintype "passive"))
      (node (ref "U19") (pin "9") (pinfunction "VD33_DAC_9") (pintype "passive"))
      (node (ref "U20") (pin "7") (pintype "passive"))
    )
    (net (code "54") (name "unconnected-(U20-Pad3)") (class "Default")
      (node (ref "U20") (pin "3") (pintype "passive"))
    )
    (net (code "55") (name "unconnected-(U20-Pad8)") (class "Default")
      (node (ref "U20") (pin "8") (pintype "passive"))
    )
    (net (code "56") (name "unconnected-(U20-Pad12)") (class "Default")
      (node (ref "U20") (pin "12") (pintype "passive"))
    )
  )
)
